# Guitar_Amp.net
KiCad netlist of a schematic drawn in Altium Designer
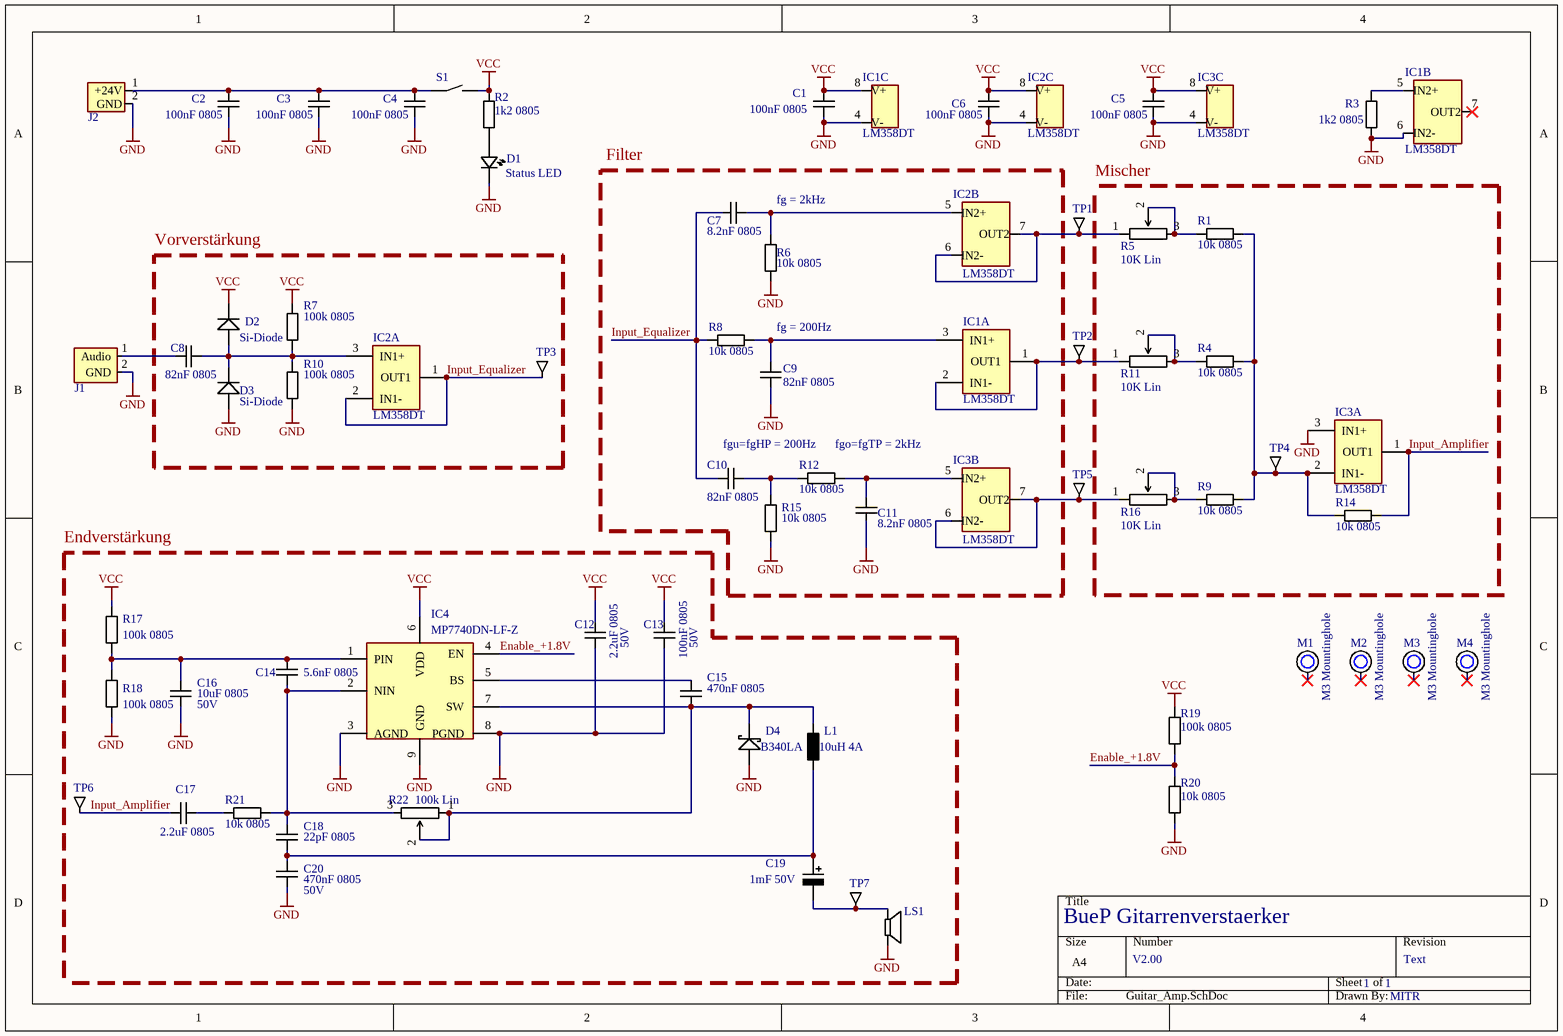
[diagram p0: Guitar_Amp.SchDoc]

(export (version "E")
  (design (tool "Eeschema 10.0.6"))
  (components
    (comp (ref "C1")
      (value "100nF 0805")
      (footprint "C Template for 0805")
      (fields
        (field (name "MANUFACTURER_PART_NUMBER") "RC0805FR-07100RP")
        (field (name "MOUSER PART NUMBER") "603-RC0805FR-07100RP")
      )
      (libsource (lib "C_100nF_0805") (part "RC0805FR-07100RP"))
    )
    (comp (ref "C2")
      (value "100nF 0805")
      (footprint "C Template for 0805")
      (fields
        (field (name "MANUFACTURER_PART_NUMBER") "RC0805FR-07100RP")
        (field (name "MOUSER PART NUMBER") "603-RC0805FR-07100RP")
      )
      (libsource (lib "C_100nF_0805") (part "RC0805FR-07100RP"))
    )
    (comp (ref "C3")
      (value "100nF 0805")
      (footprint "C Template for 0805")
      (fields
        (field (name "MANUFACTURER_PART_NUMBER") "RC0805FR-07100RP")
        (field (name "MOUSER PART NUMBER") "603-RC0805FR-07100RP")
      )
      (libsource (lib "C_100nF_0805") (part "RC0805FR-07100RP"))
    )
    (comp (ref "C4")
      (value "100nF 0805")
      (footprint "C Template for 0805")
      (fields
        (field (name "MANUFACTURER_PART_NUMBER") "RC0805FR-07100RP")
        (field (name "MOUSER PART NUMBER") "603-RC0805FR-07100RP")
      )
      (libsource (lib "C_100nF_0805") (part "RC0805FR-07100RP"))
    )
    (comp (ref "C5")
      (value "100nF 0805")
      (footprint "C Template for 0805")
      (fields
        (field (name "MANUFACTURER_PART_NUMBER") "RC0805FR-07100RP")
        (field (name "MOUSER PART NUMBER") "603-RC0805FR-07100RP")
      )
      (libsource (lib "C_100nF_0805") (part "RC0805FR-07100RP"))
    )
    (comp (ref "C6")
      (value "100nF 0805")
      (footprint "C Template for 0805")
      (fields
        (field (name "MANUFACTURER_PART_NUMBER") "RC0805FR-07100RP")
        (field (name "MOUSER PART NUMBER") "603-RC0805FR-07100RP")
      )
      (libsource (lib "C_100nF_0805") (part "RC0805FR-07100RP"))
    )
    (comp (ref "C7")
      (value "8.2nF 0805")
      (footprint "C Template for 0805")
      (fields
        (field (name "MANUFACTURER_PART_NUMBER") "RC0805FR-07100RP")
        (field (name "MOUSER PART NUMBER") "603-RC0805FR-07100RP")
      )
      (libsource (lib "C_8_2nF_0805") (part "RC0805FR-07100RP"))
    )
    (comp (ref "C8")
      (value "82nF 0805")
      (footprint "C Template for 0805")
      (fields
        (field (name "MANUFACTURER_PART_NUMBER") "RC0805FR-07100RP")
        (field (name "MOUSER PART NUMBER") "603-RC0805FR-07100RP")
      )
      (libsource (lib "C_82nF_0805") (part "RC0805FR-07100RP"))
    )
    (comp (ref "C9")
      (value "82nF 0805")
      (footprint "C Template for 0805")
      (fields
        (field (name "MANUFACTURER_PART_NUMBER") "RC0805FR-07100RP")
        (field (name "MOUSER PART NUMBER") "603-RC0805FR-07100RP")
      )
      (libsource (lib "C_82nF_0805") (part "RC0805FR-07100RP"))
    )
    (comp (ref "C10")
      (value "82nF 0805")
      (footprint "C Template for 0805")
      (fields
        (field (name "MANUFACTURER_PART_NUMBER") "RC0805FR-07100RP")
        (field (name "MOUSER PART NUMBER") "603-RC0805FR-07100RP")
      )
      (libsource (lib "C_82nF_0805") (part "RC0805FR-07100RP"))
    )
    (comp (ref "C11")
      (value "8.2nF 0805")
      (footprint "C Template for 0805")
      (fields
        (field (name "MANUFACTURER_PART_NUMBER") "RC0805FR-07100RP")
        (field (name "MOUSER PART NUMBER") "603-RC0805FR-07100RP")
      )
      (libsource (lib "C_8_2nF_0805") (part "RC0805FR-07100RP"))
    )
    (comp (ref "C12")
      (value "2.2uF 0805")
      (footprint "C Template for 0805")
      (fields
        (field (name "MANUFACTURER_PART_NUMBER") "RC0805FR-07100RP")
        (field (name "MOUSER PART NUMBER") "603-RC0805FR-07100RP")
      )
      (libsource (lib "C_2_2uF_0805") (part "2.2uF 0805"))
    )
    (comp (ref "C13")
      (value "100nF 0805")
      (footprint "C Template for 0805")
      (fields
        (field (name "MANUFACTURER_PART_NUMBER") "RC0805FR-07100RP")
        (field (name "MOUSER PART NUMBER") "603-RC0805FR-07100RP")
      )
      (libsource (lib "C_100nF_0805") (part "RC0805FR-07100RP"))
    )
    (comp (ref "C14")
      (value "5.6nF 0805")
      (footprint "C Template for 0805")
      (fields
        (field (name "MANUFACTURER_PART_NUMBER") "RC0805FR-07100RP")
        (field (name "MOUSER PART NUMBER") "603-RC0805FR-07100RP")
      )
      (libsource (lib "C_5_6nF_0805") (part "RC0805FR-07100RP"))
    )
    (comp (ref "C15")
      (value "470nF 0805")
      (footprint "C Template for 0805")
      (fields
        (field (name "MANUFACTURER_PART_NUMBER") "RC0805FR-07100RP")
        (field (name "MOUSER PART NUMBER") "603-RC0805FR-07100RP")
      )
      (libsource (lib "C_470nF_0805") (part "RC0805FR-07100RP"))
    )
    (comp (ref "C16")
      (value "10uF 0805")
      (footprint "C Template for 0805")
      (fields
        (field (name "MANUFACTURER_PART_NUMBER") "RC0805FR-07100RP")
        (field (name "MOUSER PART NUMBER") "603-RC0805FR-07100RP")
      )
      (libsource (lib "C_10uF_0805") (part "RC0805FR-07100RP"))
    )
    (comp (ref "C17")
      (value "2.2uF 0805")
      (footprint "C Template for 0805")
      (fields
        (field (name "MANUFACTURER_PART_NUMBER") "RC0805FR-07100RP")
        (field (name "MOUSER PART NUMBER") "603-RC0805FR-07100RP")
      )
      (libsource (lib "C_2_2uF_0805") (part "2.2uF 0805"))
    )
    (comp (ref "C18")
      (value "22pF 0805")
      (footprint "C Template for 0805")
      (fields
        (field (name "MANUFACTURER_PART_NUMBER") "RC0805FR-07100RP")
        (field (name "MOUSER PART NUMBER") "603-RC0805FR-07100RP")
      )
      (libsource (lib "C_22pF_0805") (part "RC0805FR-07100RP"))
    )
    (comp (ref "C19")
      (value "1mF 50V")
      (footprint "C 1mF 50V Elko")
      (description "Mono Audio Input-Jack of Guitar")
      (fields
        (field (name "MANUFACTURER_PART_NUMBER") "RC0805FR-07100RP")
        (field (name "MOUSER PART NUMBER") "603-RC0805FR-07100RP")
      )
      (libsource (lib "C_1mF_Elko_50V") (part "Electrolyte Capacitor"))
    )
    (comp (ref "C20")
      (value "470nF 0805")
      (footprint "C Template for 0805")
      (fields
        (field (name "MANUFACTURER_PART_NUMBER") "RC0805FR-07100RP")
        (field (name "MOUSER PART NUMBER") "603-RC0805FR-07100RP")
      )
      (libsource (lib "C_470nF_0805") (part "RC0805FR-07100RP"))
    )
    (comp (ref "D1")
      (value "?F")
      (footprint "5mm LED Red")
      (description "5mm LED red")
      (fields
        (field (name "MANUFACTURER_PART_NUMBER") "RC0805FR-07100RP")
        (field (name "MOUSER PART NUMBER") "603-RC0805FR-07100RP")
      )
      (libsource (lib "5mm_LED_Red") (part "5mm LED red"))
    )
    (comp (ref "D2")
      (value "Si-Diode")
      (footprint "Si-Diode Footprint")
      (fields
        (field (name "MANUFACTURER_PART_NUMBER") "RC0805FR-07100RP")
        (field (name "MOUSER PART NUMBER") "603-RC0805FR-07100RP")
      )
      (libsource (lib "Si_Diode") (part "Si-Diode"))
    )
    (comp (ref "D3")
      (value "Si-Diode")
      (footprint "Si-Diode Footprint")
      (fields
        (field (name "MANUFACTURER_PART_NUMBER") "RC0805FR-07100RP")
        (field (name "MOUSER PART NUMBER") "603-RC0805FR-07100RP")
      )
      (libsource (lib "Si_Diode") (part "Si-Diode"))
    )
    (comp (ref "D4")
      (value "B340LA")
      (footprint "B340LA-13-F Schottky Diode")
      (description "BL340LA-13-F SMA-Package")
      (fields
        (field (name "MANUFACTURER_PART_NUMBER") "RC0805FR-07100RP")
        (field (name "MOUSER PART NUMBER") "603-RC0805FR-07100RP")
      )
      (libsource (lib "B340LA-13-F") (part "BL340LA-13-F"))
    )
    (comp (ref "IC1")
      (value "LM358DT")
      (footprint "SOIC127P600X175-8N")
      (description "LM358DT, Dual Operational Amplifier 1.1MHz 5 to 28V, 8-Pin SO")
      (fields (field (name "MOUSER PART NUMBER") "511-LM358DT"))
      (libsource (lib "LM358DT") (part "LM358DT"))
    )
    (comp (ref "IC2")
      (value "LM358DT")
      (footprint "SOIC127P600X175-8N")
      (description "LM358DT, Dual Operational Amplifier 1.1MHz 5 to 28V, 8-Pin SO")
      (fields (field (name "MOUSER PART NUMBER") "511-LM358DT"))
      (libsource (lib "LM358DT") (part "LM358DT"))
    )
    (comp (ref "IC3")
      (value "LM358DT")
      (footprint "SOIC127P600X175-8N")
      (description "LM358DT, Dual Operational Amplifier 1.1MHz 5 to 28V, 8-Pin SO")
      (fields (field (name "MOUSER PART NUMBER") "511-LM358DT"))
      (libsource (lib "LM358DT") (part "LM358DT"))
    )
    (comp (ref "IC4")
      (value "MP7740DN-LF-Z")
      (footprint "SOIC127P600X170-9N")
      (description "Audio Amplifiers 15W Class-D Mono Single End Audio Amp")
      (fields (field (name "MOUSER PART NUMBER") "946-MP7740DNLFZ"))
      (libsource (lib "MP7740DN-LF-Z") (part "MP7740DN-LF-Z"))
    )
    (comp (ref "J1")
      (value "Audio-Jack")
      (footprint "Audio Inputjack")
      (description "Mono Audio Input-Jack of Guitar")
      (fields
        (field (name "MANUFACTURER_PART_NUMBER") "RC0805FR-07100RP")
        (field (name "MOUSER PART NUMBER") "603-RC0805FR-07100RP")
      )
      (libsource (lib "Audio_Inputjack") (part "Audio-Jack"))
    )
    (comp (ref "J2")
      (value "?F 080")
      (footprint "Power Supply Input")
      (fields
        (field (name "MANUFACTURER_PART_NUMBER") "RC0805FR-07100RP")
        (field (name "MOUSER PART NUMBER") "603-RC0805FR-07100RP")
      )
      (libsource (lib "Power_Supply_Input") (part "Power Supply Input Socket"))
    )
    (comp (ref "L1")
      (value "10uH 4A")
      (footprint "Inductor 10uH / 4A")
      (fields
        (field (name "MANUFACTURER_PART_NUMBER") "RC0805FR-07100RP")
        (field (name "MOUSER PART NUMBER") "603-RC0805FR-07100RP")
      )
      (libsource (lib "L_10uH_4A") (part "RC0805FR-07100RP"))
    )
    (comp (ref "LS1")
      (value "4 Ohm")
      (footprint "4_Ohm_Speaker")
      (description "4 Ohm Speaker")
      (fields
        (field (name "MANUFACTURER_PART_NUMBER") "RC0805FR-07100RP")
        (field (name "MOUSER PART NUMBER") "603-RC0805FR-07100RP")
      )
      (libsource (lib "4_ohm_speaker") (part "4 Ohm Speaker"))
    )
    (comp (ref "M1")
      (value "M3 Mountinghole")
      (footprint "M3 Moutinghole")
      (fields
        (field (name "MANUFACTURER_PART_NUMBER") "RC0805FR-07100RP")
        (field (name "MOUSER PART NUMBER") "603-RC0805FR-07100RP")
      )
      (libsource (lib "M3_Mountinghole") (part "M3 Mountinghole"))
    )
    (comp (ref "M2")
      (value "M3 Mountinghole")
      (footprint "M3 Moutinghole")
      (fields
        (field (name "MANUFACTURER_PART_NUMBER") "RC0805FR-07100RP")
        (field (name "MOUSER PART NUMBER") "603-RC0805FR-07100RP")
      )
      (libsource (lib "M3_Mountinghole") (part "M3 Mountinghole"))
    )
    (comp (ref "M3")
      (value "M3 Mountinghole")
      (footprint "M3 Moutinghole")
      (fields
        (field (name "MANUFACTURER_PART_NUMBER") "RC0805FR-07100RP")
        (field (name "MOUSER PART NUMBER") "603-RC0805FR-07100RP")
      )
      (libsource (lib "M3_Mountinghole") (part "M3 Mountinghole"))
    )
    (comp (ref "M4")
      (value "M3 Mountinghole")
      (footprint "M3 Moutinghole")
      (fields
        (field (name "MANUFACTURER_PART_NUMBER") "RC0805FR-07100RP")
        (field (name "MOUSER PART NUMBER") "603-RC0805FR-07100RP")
      )
      (libsource (lib "M3_Mountinghole") (part "M3 Mountinghole"))
    )
    (comp (ref "R1")
      (value "10k 0805")
      (footprint "R Template for 0805")
      (fields
        (field (name "MANUFACTURER_PART_NUMBER") "RC0805FR-07100RP")
        (field (name "MOUSER PART NUMBER") "603-RC0805FR-07100RP")
      )
      (libsource (lib "R_10k_0805") (part "RC0805FR-07100RP"))
    )
    (comp (ref "R2")
      (value "1k2 0805")
      (footprint "R Template for 0805")
      (fields
        (field (name "MANUFACTURER_PART_NUMBER") "RC0805FR-07100RP")
        (field (name "MOUSER PART NUMBER") "603-RC0805FR-07100RP")
      )
      (libsource (lib "R_1k2_0805") (part "RC0805FR-07100RP"))
    )
    (comp (ref "R3")
      (value "1k2 0805")
      (footprint "R Template for 0805")
      (fields
        (field (name "MANUFACTURER_PART_NUMBER") "RC0805FR-07100RP")
        (field (name "MOUSER PART NUMBER") "603-RC0805FR-07100RP")
      )
      (libsource (lib "R_1k2_0805") (part "RC0805FR-07100RP"))
    )
    (comp (ref "R4")
      (value "10k 0805")
      (footprint "R Template for 0805")
      (fields
        (field (name "MANUFACTURER_PART_NUMBER") "RC0805FR-07100RP")
        (field (name "MOUSER PART NUMBER") "603-RC0805FR-07100RP")
      )
      (libsource (lib "R_10k_0805") (part "RC0805FR-07100RP"))
    )
    (comp (ref "R5")
      (value "10K Lin")
      (footprint "Poti_standard_footprint")
      (fields
        (field (name "MANUFACTURER_PART_NUMBER") "RC0805FR-07100RP")
        (field (name "MOUSER PART NUMBER") "603-RC0805FR-07100RP")
      )
      (libsource (lib "10K_Poti") (part "10k Linear Potentiometer"))
    )
    (comp (ref "R6")
      (value "10k 0805")
      (footprint "R Template for 0805")
      (fields
        (field (name "MANUFACTURER_PART_NUMBER") "RC0805FR-07100RP")
        (field (name "MOUSER PART NUMBER") "603-RC0805FR-07100RP")
      )
      (libsource (lib "") (part "RC0805FR-07100RP_1"))
    )
    (comp (ref "R7")
      (value "100k 0805")
      (footprint "R Template for 0805")
      (fields
        (field (name "MANUFACTURER_PART_NUMBER") "RC0805FR-07100RP")
        (field (name "MOUSER PART NUMBER") "603-RC0805FR-07100RP")
      )
      (libsource (lib "R_100k_0805") (part "RC0805FR-07100RP"))
    )
    (comp (ref "R8")
      (value "10k 0805")
      (footprint "R Template for 0805")
      (fields
        (field (name "MANUFACTURER_PART_NUMBER") "RC0805FR-07100RP")
        (field (name "MOUSER PART NUMBER") "603-RC0805FR-07100RP")
      )
      (libsource (lib "R_10k_0805") (part "RC0805FR-07100RP"))
    )
    (comp (ref "R9")
      (value "10k 0805")
      (footprint "R Template for 0805")
      (fields
        (field (name "MANUFACTURER_PART_NUMBER") "RC0805FR-07100RP")
        (field (name "MOUSER PART NUMBER") "603-RC0805FR-07100RP")
      )
      (libsource (lib "R_10k_0805") (part "RC0805FR-07100RP"))
    )
    (comp (ref "R10")
      (value "100k 0805")
      (footprint "R Template for 0805")
      (fields
        (field (name "MANUFACTURER_PART_NUMBER") "RC0805FR-07100RP")
        (field (name "MOUSER PART NUMBER") "603-RC0805FR-07100RP")
      )
      (libsource (lib "R_100k_0805") (part "RC0805FR-07100RP"))
    )
    (comp (ref "R11")
      (value "10K Lin")
      (footprint "Poti_standard_footprint")
      (fields
        (field (name "MANUFACTURER_PART_NUMBER") "RC0805FR-07100RP")
        (field (name "MOUSER PART NUMBER") "603-RC0805FR-07100RP")
      )
      (libsource (lib "10K_Poti") (part "10k Linear Potentiometer"))
    )
    (comp (ref "R12")
      (value "10k 0805")
      (footprint "R Template for 0805")
      (fields
        (field (name "MANUFACTURER_PART_NUMBER") "RC0805FR-07100RP")
        (field (name "MOUSER PART NUMBER") "603-RC0805FR-07100RP")
      )
      (libsource (lib "") (part "RC0805FR-07100RP_2"))
    )
    (comp (ref "R14")
      (value "10k 0805")
      (footprint "R Template for 0805")
      (fields
        (field (name "MANUFACTURER_PART_NUMBER") "RC0805FR-07100RP")
        (field (name "MOUSER PART NUMBER") "603-RC0805FR-07100RP")
      )
      (libsource (lib "") (part "RC0805FR-07100RP_2"))
    )
    (comp (ref "R15")
      (value "10k 0805")
      (footprint "R Template for 0805")
      (fields
        (field (name "MANUFACTURER_PART_NUMBER") "RC0805FR-07100RP")
        (field (name "MOUSER PART NUMBER") "603-RC0805FR-07100RP")
      )
      (libsource (lib "") (part "RC0805FR-07100RP_1"))
    )
    (comp (ref "R16")
      (value "10K Lin")
      (footprint "Poti_standard_footprint")
      (fields
        (field (name "MANUFACTURER_PART_NUMBER") "RC0805FR-07100RP")
        (field (name "MOUSER PART NUMBER") "603-RC0805FR-07100RP")
      )
      (libsource (lib "10K_Poti") (part "10k Linear Potentiometer"))
    )
    (comp (ref "R17")
      (value "100k 0805")
      (footprint "R Template for 0805")
      (fields
        (field (name "MANUFACTURER_PART_NUMBER") "RC0805FR-07100RP")
        (field (name "MOUSER PART NUMBER") "603-RC0805FR-07100RP")
      )
      (libsource (lib "R_100k_0805") (part "RC0805FR-07100RP"))
    )
    (comp (ref "R18")
      (value "100k 0805")
      (footprint "R Template for 0805")
      (fields
        (field (name "MANUFACTURER_PART_NUMBER") "RC0805FR-07100RP")
        (field (name "MOUSER PART NUMBER") "603-RC0805FR-07100RP")
      )
      (libsource (lib "R_100k_0805") (part "RC0805FR-07100RP"))
    )
    (comp (ref "R19")
      (value "100k 0805")
      (footprint "R Template for 0805")
      (fields
        (field (name "MANUFACTURER_PART_NUMBER") "RC0805FR-07100RP")
        (field (name "MOUSER PART NUMBER") "603-RC0805FR-07100RP")
      )
      (libsource (lib "R_100k_0805") (part "RC0805FR-07100RP"))
    )
    (comp (ref "R20")
      (value "10k 0805")
      (footprint "R Template for 0805")
      (fields
        (field (name "MANUFACTURER_PART_NUMBER") "RC0805FR-07100RP")
        (field (name "MOUSER PART NUMBER") "603-RC0805FR-07100RP")
      )
      (libsource (lib "") (part "RC0805FR-07100RP_1"))
    )
    (comp (ref "R21")
      (value "10k 0805")
      (footprint "R Template for 0805")
      (fields
        (field (name "MANUFACTURER_PART_NUMBER") "RC0805FR-07100RP")
        (field (name "MOUSER PART NUMBER") "603-RC0805FR-07100RP")
      )
      (libsource (lib "") (part "RC0805FR-07100RP_2"))
    )
    (comp (ref "R22")
      (value "100k Lin")
      (footprint "Poti_standard_footprint")
      (fields
        (field (name "MANUFACTURER_PART_NUMBER") "RC0805FR-07100RP")
        (field (name "MOUSER PART NUMBER") "603-RC0805FR-07100RP")
      )
      (libsource (lib "100k_Poti") (part "100k Linear Potentiometer"))
    )
    (comp (ref "S1")
      (value "?H 0805")
      (footprint "Switch")
      (fields
        (field (name "MANUFACTURER_PART_NUMBER") "RC0805FR-07100RP")
        (field (name "MOUSER PART NUMBER") "603-RC0805FR-07100RP")
      )
      (libsource (lib "Switch") (part "Switch"))
    )
    (comp (ref "TP1")
      (value "Testpoint_2.54mm")
      (footprint "Testpoint_2.54mm")
      (fields
        (field (name "MANUFACTURER_PART_NUMBER") "RC0805FR-07100RP")
        (field (name "MOUSER PART NUMBER") "603-RC0805FR-07100RP")
      )
      (libsource (lib "Test_Point_2.54mm") (part "Testpoint_2.54mm"))
    )
    (comp (ref "TP2")
      (value "Testpoint_2.54mm")
      (footprint "Testpoint_2.54mm")
      (fields
        (field (name "MANUFACTURER_PART_NUMBER") "RC0805FR-07100RP")
        (field (name "MOUSER PART NUMBER") "603-RC0805FR-07100RP")
      )
      (libsource (lib "Test_Point_2.54mm") (part "Testpoint_2.54mm"))
    )
    (comp (ref "TP3")
      (value "Testpoint_2.54mm")
      (footprint "Testpoint_2.54mm")
      (fields
        (field (name "MANUFACTURER_PART_NUMBER") "RC0805FR-07100RP")
        (field (name "MOUSER PART NUMBER") "603-RC0805FR-07100RP")
      )
      (libsource (lib "Test_Point_2.54mm") (part "Testpoint_2.54mm"))
    )
    (comp (ref "TP4")
      (value "Testpoint_2.54mm")
      (footprint "Testpoint_2.54mm")
      (fields
        (field (name "MANUFACTURER_PART_NUMBER") "RC0805FR-07100RP")
        (field (name "MOUSER PART NUMBER") "603-RC0805FR-07100RP")
      )
      (libsource (lib "Test_Point_2.54mm") (part "Testpoint_2.54mm"))
    )
    (comp (ref "TP5")
      (value "Testpoint_2.54mm")
      (footprint "Testpoint_2.54mm")
      (fields
        (field (name "MANUFACTURER_PART_NUMBER") "RC0805FR-07100RP")
        (field (name "MOUSER PART NUMBER") "603-RC0805FR-07100RP")
      )
      (libsource (lib "Test_Point_2.54mm") (part "Testpoint_2.54mm"))
    )
    (comp (ref "TP6")
      (value "Testpoint_2.54mm")
      (footprint "Testpoint_2.54mm")
      (fields
        (field (name "MANUFACTURER_PART_NUMBER") "RC0805FR-07100RP")
        (field (name "MOUSER PART NUMBER") "603-RC0805FR-07100RP")
      )
      (libsource (lib "Test_Point_2.54mm") (part "Testpoint_2.54mm"))
    )
    (comp (ref "TP7")
      (value "Testpoint_2.54mm")
      (footprint "Testpoint_2.54mm")
      (fields
        (field (name "MANUFACTURER_PART_NUMBER") "RC0805FR-07100RP")
        (field (name "MOUSER PART NUMBER") "603-RC0805FR-07100RP")
      )
      (libsource (lib "Test_Point_2.54mm") (part "Testpoint_2.54mm"))
    )
  )
  (nets
    (net (code "1") (name "/Enable_+1.8V") (class "Default")
      (node (ref "IC4") (pin "4") (pinfunction "EN_4") (pintype "passive"))
      (node (ref "R19") (pin "1") (pintype "passive"))
      (node (ref "R20") (pin "2") (pintype "passive"))
    )
    (net (code "2") (name "/Input_Amplifier") (class "Default")
      (node (ref "C17") (pin "1") (pintype "passive"))
      (node (ref "IC3") (pin "1") (pinfunction "OUT1_1") (pintype "passive"))
      (node (ref "R14") (pin "1") (pintype "passive"))
      (node (ref "TP6") (pin "1") (pintype "passive"))
    )
    (net (code "3") (name "/Input_Equalizer") (class "Default")
      (node (ref "C10") (pin "1") (pintype "passive"))
      (node (ref "C7") (pin "1") (pintype "passive"))
      (node (ref "IC2") (pin "1") (pinfunction "OUT1_1") (pintype "passive"))
      (node (ref "IC2") (pin "2") (pinfunction "IN1-_2") (pintype "passive"))
      (node (ref "R8") (pin "1") (pintype "passive"))
      (node (ref "TP3") (pin "1") (pintype "passive"))
    )
    (net (code "4") (name "GND") (class "Default")
      (node (ref "C1") (pin "2") (pintype "passive"))
      (node (ref "C11") (pin "1") (pintype "passive"))
      (node (ref "C12") (pin "1") (pintype "passive"))
      (node (ref "C13") (pin "1") (pintype "passive"))
      (node (ref "C16") (pin "1") (pintype "passive"))
      (node (ref "C2") (pin "2") (pintype "passive"))
      (node (ref "C20") (pin "1") (pinfunction "1_1") (pintype "passive"))
      (node (ref "C3") (pin "2") (pintype "passive"))
      (node (ref "C4") (pin "2") (pintype "passive"))
      (node (ref "C5") (pin "2") (pintype "passive"))
      (node (ref "C6") (pin "2") (pintype "passive"))
      (node (ref "C9") (pin "1") (pintype "passive"))
      (node (ref "D1") (pin "2") (pinfunction "GND_2") (pintype "passive"))
      (node (ref "D3") (pin "1") (pintype "passive"))
      (node (ref "D4") (pin "1") (pintype "passive"))
      (node (ref "IC1") (pin "4") (pinfunction "V-_4") (pintype "passive"))
      (node (ref "IC1") (pin "6") (pinfunction "IN2-_6") (pintype "passive"))
      (node (ref "IC2") (pin "4") (pinfunction "V-_4") (pintype "passive"))
      (node (ref "IC3") (pin "3") (pinfunction "IN1+_3") (pintype "passive"))
      (node (ref "IC3") (pin "4") (pinfunction "V-_4") (pintype "passive"))
      (node (ref "IC4") (pin "3") (pinfunction "AGND_3") (pintype "passive"))
      (node (ref "IC4") (pin "8") (pinfunction "PGND_8") (pintype "passive"))
      (node (ref "IC4") (pin "9") (pinfunction "GND_9") (pintype "passive"))
      (node (ref "J1") (pin "2") (pinfunction "GND_2") (pintype "passive"))
      (node (ref "J2") (pin "2") (pinfunction "GND_2") (pintype "passive"))
      (node (ref "LS1") (pin "2") (pinfunction "2_2") (pintype "passive"))
      (node (ref "R10") (pin "1") (pintype "passive"))
      (node (ref "R15") (pin "1") (pintype "passive"))
      (node (ref "R18") (pin "1") (pintype "passive"))
      (node (ref "R20") (pin "1") (pintype "passive"))
      (node (ref "R3") (pin "1") (pintype "passive"))
      (node (ref "R6") (pin "1") (pintype "passive"))
    )
    (net (code "5") (name "Net-(C10-Pad2)") (class "Default")
      (node (ref "C10") (pin "2") (pintype "passive"))
      (node (ref "R12") (pin "2") (pintype "passive"))
      (node (ref "R15") (pin "2") (pintype "passive"))
    )
    (net (code "6") (name "Net-(C17-Pad2)") (class "Default")
      (node (ref "C17") (pin "2") (pintype "passive"))
      (node (ref "R21") (pin "2") (pintype "passive"))
    )
    (net (code "7") (name "Net-(C18-Pad1)") (class "Default")
      (node (ref "C18") (pin "1") (pintype "passive"))
      (node (ref "C19") (pin "1") (pintype "passive"))
      (node (ref "C20") (pin "2") (pinfunction "2_2") (pintype "passive"))
      (node (ref "L1") (pin "1") (pintype "passive"))
    )
    (net (code "8") (name "Net-(D1-+24V)") (class "Default")
      (node (ref "D1") (pin "1") (pinfunction "+24V_1") (pintype "passive"))
      (node (ref "R2") (pin "1") (pintype "passive"))
    )
    (net (code "9") (name "Net-(IC1A-IN1+)") (class "Default")
      (node (ref "C9") (pin "2") (pintype "passive"))
      (node (ref "IC1") (pin "3") (pinfunction "IN1+_3") (pintype "passive"))
      (node (ref "R8") (pin "2") (pintype "passive"))
    )
    (net (code "10") (name "Net-(IC1A-IN1-)") (class "Default")
      (node (ref "IC1") (pin "1") (pinfunction "OUT1_1") (pintype "passive"))
      (node (ref "IC1") (pin "2") (pinfunction "IN1-_2") (pintype "passive"))
      (node (ref "R11") (pin "1") (pintype "passive"))
      (node (ref "TP2") (pin "1") (pintype "passive"))
    )
    (net (code "11") (name "Net-(IC1B-IN2+)") (class "Default")
      (node (ref "IC1") (pin "5") (pinfunction "IN2+_5") (pintype "passive"))
      (node (ref "R3") (pin "2") (pintype "passive"))
    )
    (net (code "12") (name "Net-(IC2A-IN1+)") (class "Default")
      (node (ref "C8") (pin "2") (pintype "passive"))
      (node (ref "D2") (pin "1") (pintype "passive"))
      (node (ref "D3") (pin "2") (pintype "passive"))
      (node (ref "IC2") (pin "3") (pinfunction "IN1+_3") (pintype "passive"))
      (node (ref "R10") (pin "2") (pintype "passive"))
      (node (ref "R7") (pin "1") (pintype "passive"))
    )
    (net (code "13") (name "Net-(IC2B-IN2+)") (class "Default")
      (node (ref "C7") (pin "2") (pintype "passive"))
      (node (ref "IC2") (pin "5") (pinfunction "IN2+_5") (pintype "passive"))
      (node (ref "R6") (pin "2") (pintype "passive"))
    )
    (net (code "14") (name "Net-(IC2B-IN2-)") (class "Default")
      (node (ref "IC2") (pin "6") (pinfunction "IN2-_6") (pintype "passive"))
      (node (ref "IC2") (pin "7") (pinfunction "OUT2_7") (pintype "passive"))
      (node (ref "R5") (pin "1") (pintype "passive"))
      (node (ref "TP1") (pin "1") (pintype "passive"))
    )
    (net (code "15") (name "Net-(IC3A-IN1-)") (class "Default")
      (node (ref "IC3") (pin "2") (pinfunction "IN1-_2") (pintype "passive"))
      (node (ref "R1") (pin "2") (pintype "passive"))
      (node (ref "R14") (pin "2") (pintype "passive"))
      (node (ref "R4") (pin "2") (pintype "passive"))
      (node (ref "R9") (pin "2") (pintype "passive"))
      (node (ref "TP4") (pin "1") (pintype "passive"))
    )
    (net (code "16") (name "Net-(IC3B-IN2+)") (class "Default")
      (node (ref "C11") (pin "2") (pintype "passive"))
      (node (ref "IC3") (pin "5") (pinfunction "IN2+_5") (pintype "passive"))
      (node (ref "R12") (pin "1") (pintype "passive"))
    )
    (net (code "17") (name "Net-(IC3B-IN2-)") (class "Default")
      (node (ref "IC3") (pin "6") (pinfunction "IN2-_6") (pintype "passive"))
      (node (ref "IC3") (pin "7") (pinfunction "OUT2_7") (pintype "passive"))
      (node (ref "R16") (pin "1") (pintype "passive"))
      (node (ref "TP5") (pin "1") (pintype "passive"))
    )
    (net (code "18") (name "Net-(IC4-BS)") (class "Default")
      (node (ref "C15") (pin "2") (pinfunction "2_2") (pintype "passive"))
      (node (ref "IC4") (pin "5") (pinfunction "BS_5") (pintype "passive"))
    )
    (net (code "19") (name "Net-(IC4-NIN)") (class "Default")
      (node (ref "C14") (pin "1") (pintype "passive"))
      (node (ref "C18") (pin "2") (pintype "passive"))
      (node (ref "IC4") (pin "2") (pinfunction "NIN_2") (pintype "passive"))
      (node (ref "R21") (pin "1") (pintype "passive"))
      (node (ref "R22") (pin "3") (pinfunction "OUT9_3") (pintype "passive"))
    )
    (net (code "20") (name "Net-(IC4-PIN)") (class "Default")
      (node (ref "C14") (pin "2") (pintype "passive"))
      (node (ref "C16") (pin "2") (pintype "passive"))
      (node (ref "IC4") (pin "1") (pinfunction "PIN_1") (pintype "passive"))
      (node (ref "R17") (pin "1") (pintype "passive"))
      (node (ref "R18") (pin "2") (pintype "passive"))
    )
    (net (code "21") (name "Net-(IC4-SW)") (class "Default")
      (node (ref "C15") (pin "1") (pinfunction "1_1") (pintype "passive"))
      (node (ref "D4") (pin "2") (pintype "passive"))
      (node (ref "IC4") (pin "7") (pinfunction "SW_7") (pintype "passive"))
      (node (ref "L1") (pin "2") (pintype "passive"))
      (node (ref "R22") (pin "1") (pintype "passive"))
      (node (ref "R22") (pin "2") (pinfunction "5_2") (pintype "passive"))
    )
    (net (code "22") (name "Net-(J1-Audio)") (class "Default")
      (node (ref "C8") (pin "1") (pintype "passive"))
      (node (ref "J1") (pin "1") (pinfunction "Audio_1") (pintype "passive"))
    )
    (net (code "23") (name "Net-(J2-+24V)") (class "Default")
      (node (ref "C2") (pin "1") (pintype "passive"))
      (node (ref "C3") (pin "1") (pintype "passive"))
      (node (ref "C4") (pin "1") (pintype "passive"))
      (node (ref "J2") (pin "1") (pinfunction "+24V_1") (pintype "passive"))
      (node (ref "S1") (pin "2") (pintype "passive"))
    )
    (net (code "24") (name "Net-(LS1-8)") (class "Default")
      (node (ref "C19") (pin "2") (pintype "passive"))
      (node (ref "LS1") (pin "1") (pinfunction "8_1") (pintype "passive"))
      (node (ref "TP7") (pin "1") (pintype "passive"))
    )
    (net (code "25") (name "Net-(R5-5)") (class "Default")
      (node (ref "R1") (pin "1") (pintype "passive"))
      (node (ref "R5") (pin "2") (pinfunction "5_2") (pintype "passive"))
      (node (ref "R5") (pin "3") (pinfunction "OUT9_3") (pintype "passive"))
    )
    (net (code "26") (name "Net-(R11-5)") (class "Default")
      (node (ref "R11") (pin "2") (pinfunction "5_2") (pintype "passive"))
      (node (ref "R11") (pin "3") (pinfunction "OUT9_3") (pintype "passive"))
      (node (ref "R4") (pin "1") (pintype "passive"))
    )
    (net (code "27") (name "Net-(R16-5)") (class "Default")
      (node (ref "R16") (pin "2") (pinfunction "5_2") (pintype "passive"))
      (node (ref "R16") (pin "3") (pinfunction "OUT9_3") (pintype "passive"))
      (node (ref "R9") (pin "1") (pintype "passive"))
    )
    (net (code "28") (name "VCC") (class "Default")
      (node (ref "C1") (pin "1") (pintype "passive"))
      (node (ref "C12") (pin "2") (pintype "passive"))
      (node (ref "C13") (pin "2") (pintype "passive"))
      (node (ref "C5") (pin "1") (pintype "passive"))
      (node (ref "C6") (pin "1") (pintype "passive"))
      (node (ref "D2") (pin "2") (pintype "passive"))
      (node (ref "IC1") (pin "8") (pinfunction "V+_8") (pintype "passive"))
      (node (ref "IC2") (pin "8") (pinfunction "V+_8") (pintype "passive"))
      (node (ref "IC3") (pin "8") (pinfunction "V+_8") (pintype "passive"))
      (node (ref "IC4") (pin "6") (pinfunction "VDD_6") (pintype "passive"))
      (node (ref "R17") (pin "2") (pintype "passive"))
      (node (ref "R19") (pin "2") (pintype "passive"))
      (node (ref "R2") (pin "2") (pintype "passive"))
      (node (ref "R7") (pin "2") (pintype "passive"))
      (node (ref "S1") (pin "1") (pintype "passive"))
    )
    (net (code "29") (name "unconnected-(IC1B-OUT2-Pad7)") (class "Default")
      (node (ref "IC1") (pin "7") (pinfunction "OUT2_7") (pintype "passive+no_connect"))
    )
    (net (code "30") (name "unconnected-(M1-Pad1)") (class "Default")
      (node (ref "M1") (pin "1") (pintype "passive+no_connect"))
    )
    (net (code "31") (name "unconnected-(M2-Pad1)") (class "Default")
      (node (ref "M2") (pin "1") (pintype "passive+no_connect"))
    )
    (net (code "32") (name "unconnected-(M3-Pad1)") (class "Default")
      (node (ref "M3") (pin "1") (pintype "passive+no_connect"))
    )
    (net (code "33") (name "unconnected-(M4-Pad1)") (class "Default")
      (node (ref "M4") (pin "1") (pintype "passive+no_connect"))
    )
  )
)
